# lisa_mac_adb.net
KiCad netlist of a schematic drawn in EAGLE
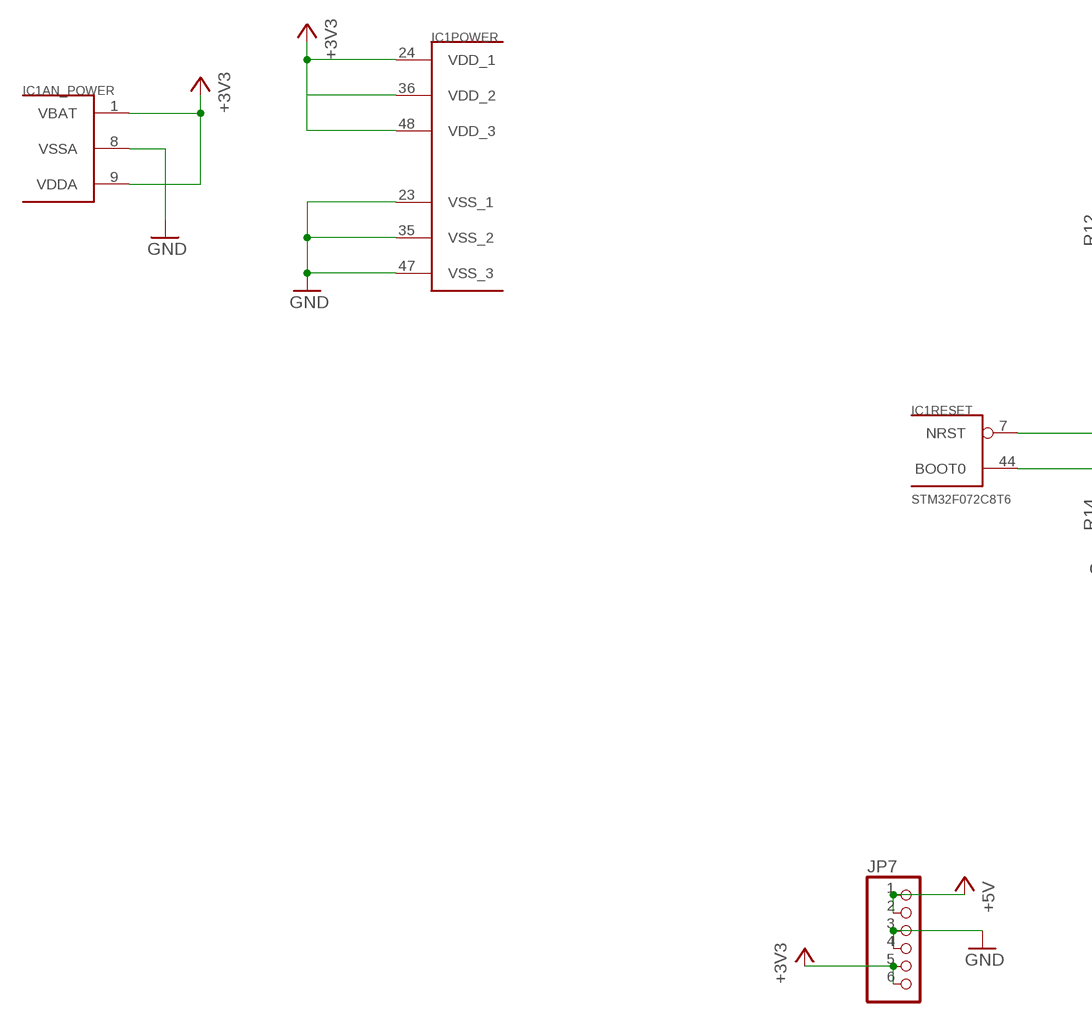
[diagram p0: schematic, sheet 1, part 1 of 2]
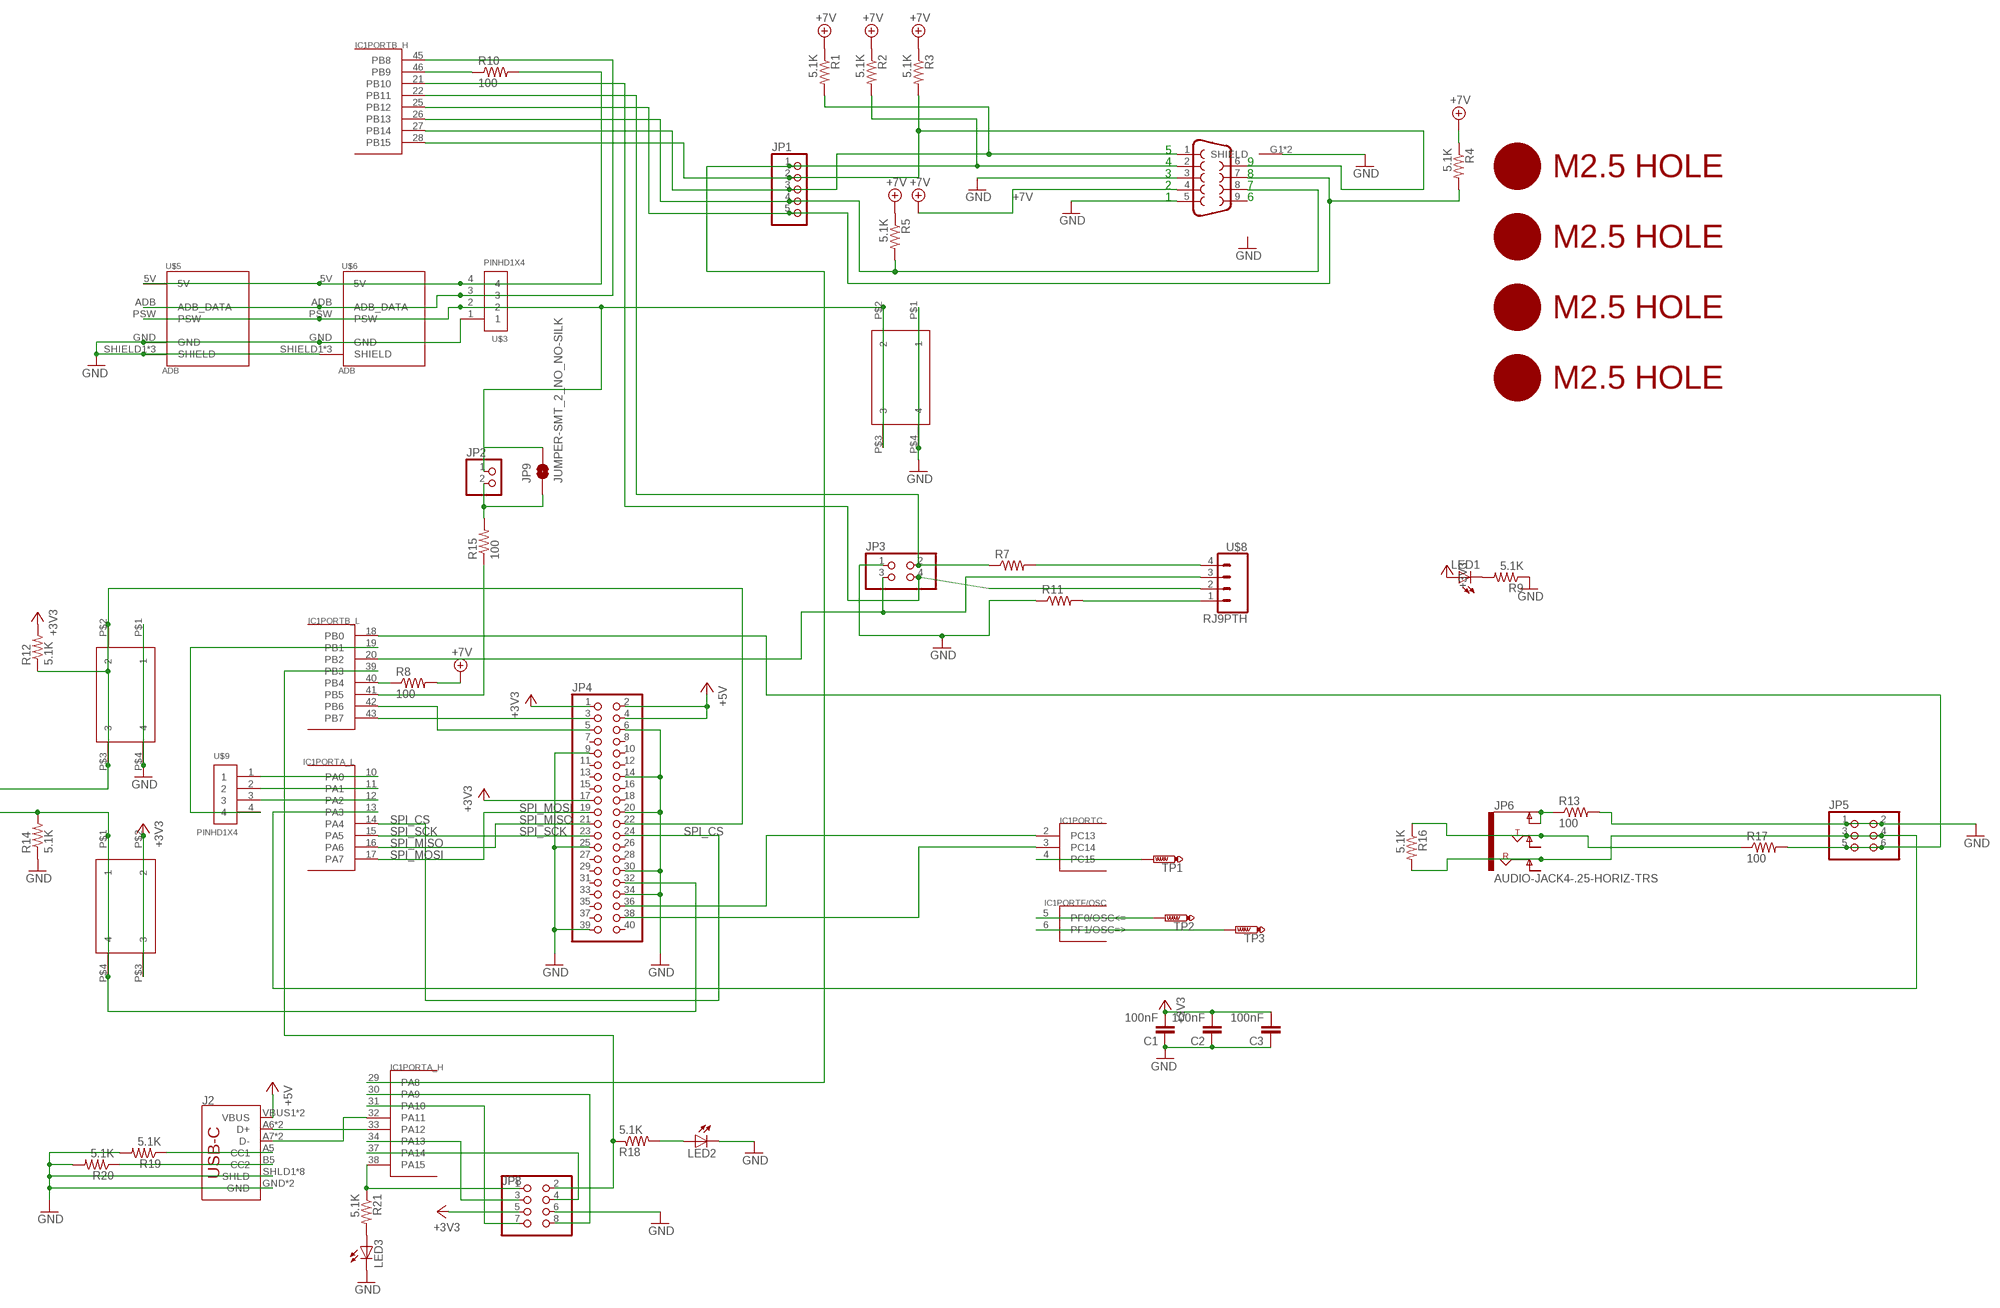
[diagram p1: schematic, sheet 1, part 2 of 2]

(export (version "E")
  (design (tool "Eeschema 10.0.6"))
  (components
    (comp (ref "C1")
      (value "100nF")
      (footprint "eagle-import:0805@1")
      (libsource (lib "eagle-import") (part "CAP0805"))
    )
    (comp (ref "C2")
      (value "100nF")
      (footprint "eagle-import:0805@1")
      (libsource (lib "eagle-import") (part "CAP0805"))
    )
    (comp (ref "C3")
      (value "100nF")
      (footprint "eagle-import:0805@1")
      (libsource (lib "eagle-import") (part "CAP0805"))
    )
    (comp (ref "IC1")
      (value "STM32F072C8T6")
      (footprint "eagle-import:TQFP48")
      (libsource (lib "eagle-import") (part "STM32F072C8T6"))
    )
    (comp (ref "J1")
      (value "DB9FEMALE")
      (footprint "eagle-import:DB9")
      (libsource (lib "eagle-import") (part "DB9FEMALE"))
    )
    (comp (ref "J2")
      (value "USB_C16PIN")
      (footprint "eagle-import:USB-C-16P")
      (libsource (lib "eagle-import") (part "USB_C16PIN"))
    )
    (comp (ref "JP1")
      (value "PINHD-1X5")
      (footprint "eagle-import:1X05")
      (libsource (lib "eagle-import") (part "PINHD-1X5"))
    )
    (comp (ref "JP2")
      (value "PINHD-1X2")
      (footprint "eagle-import:1X02")
      (libsource (lib "eagle-import") (part "PINHD-1X2"))
    )
    (comp (ref "JP3")
      (value "PINHD-2X2")
      (footprint "eagle-import:2X02")
      (libsource (lib "eagle-import") (part "PINHD-2X2"))
    )
    (comp (ref "JP4")
      (value "PINHD-2X20-BIG")
      (footprint "eagle-import:2X20-BIG")
      (libsource (lib "eagle-import") (part "PINHD-2X20-BIG"))
    )
    (comp (ref "JP5")
      (value "PINHD-2X3")
      (footprint "eagle-import:2X03")
      (libsource (lib "eagle-import") (part "PINHD-2X3"))
    )
    (comp (ref "JP6")
      (value "AUDIO-JACK4-.25-HORIZ-TRS")
      (footprint "eagle-import:AUDIO-JACK-.25-INCH-HORIZ-PTH")
      (libsource (lib "eagle-import") (part "AUDIO-JACK4-.25-HORIZ-TRS"))
    )
    (comp (ref "JP7")
      (value "PINHD-1X6CB")
      (footprint "eagle-import:1X06-CLEANBIG")
      (libsource (lib "eagle-import") (part "PINHD-1X6CB"))
    )
    (comp (ref "JP8")
      (value "PINHD-2X4")
      (footprint "eagle-import:2X04")
      (libsource (lib "eagle-import") (part "PINHD-2X4"))
    )
    (comp (ref "JP9")
      (value "JUMPER-SMT_2_NO_NO-SILK")
      (footprint "eagle-import:SMT-JUMPER_2_NO_NO-SILK")
      (libsource (lib "eagle-import") (part "JUMPER-SMT_2_NO_NO-SILK"))
    )
    (comp (ref "LED1")
      (value "LEDCHIP-LED0805")
      (footprint "eagle-import:CHIP-LED0805")
      (libsource (lib "eagle-import") (part "LEDCHIP-LED0805"))
    )
    (comp (ref "LED2")
      (value "LEDCHIP-LED0805")
      (footprint "eagle-import:CHIP-LED0805")
      (libsource (lib "eagle-import") (part "LEDCHIP-LED0805"))
    )
    (comp (ref "LED3")
      (value "LEDCHIP-LED0805")
      (footprint "eagle-import:CHIP-LED0805")
      (libsource (lib "eagle-import") (part "LEDCHIP-LED0805"))
    )
    (comp (ref "R1")
      (value "5.1K")
      (footprint "eagle-import:0805")
      (libsource (lib "eagle-import") (part "RESISTOR0805-RES"))
    )
    (comp (ref "R2")
      (value "5.1K")
      (footprint "eagle-import:0805")
      (libsource (lib "eagle-import") (part "RESISTOR0805-RES"))
    )
    (comp (ref "R3")
      (value "5.1K")
      (footprint "eagle-import:0805")
      (libsource (lib "eagle-import") (part "RESISTOR0805-RES"))
    )
    (comp (ref "R4")
      (value "5.1K")
      (footprint "eagle-import:0805")
      (libsource (lib "eagle-import") (part "RESISTOR0805-RES"))
    )
    (comp (ref "R5")
      (value "5.1K")
      (footprint "eagle-import:0805")
      (libsource (lib "eagle-import") (part "RESISTOR0805-RES"))
    )
    (comp (ref "R7")
      (value "100")
      (footprint "eagle-import:0805")
      (libsource (lib "eagle-import") (part "RESISTOR0805-RES"))
    )
    (comp (ref "R8")
      (value "100")
      (footprint "eagle-import:0805")
      (libsource (lib "eagle-import") (part "RESISTOR0805-RES"))
    )
    (comp (ref "R9")
      (value "5.1K")
      (footprint "eagle-import:0805")
      (libsource (lib "eagle-import") (part "RESISTOR0805-RES"))
    )
    (comp (ref "R10")
      (value "100")
      (footprint "eagle-import:0805")
      (libsource (lib "eagle-import") (part "RESISTOR0805-RES"))
    )
    (comp (ref "R11")
      (value "100")
      (footprint "eagle-import:0805")
      (libsource (lib "eagle-import") (part "RESISTOR0805-RES"))
    )
    (comp (ref "R12")
      (value "5.1K")
      (footprint "eagle-import:0805")
      (libsource (lib "eagle-import") (part "RESISTOR0805-RES"))
    )
    (comp (ref "R13")
      (value "100")
      (footprint "eagle-import:0805")
      (libsource (lib "eagle-import") (part "RESISTOR0805-RES"))
    )
    (comp (ref "R14")
      (value "5.1K")
      (footprint "eagle-import:0805")
      (libsource (lib "eagle-import") (part "RESISTOR0805-RES"))
    )
    (comp (ref "R15")
      (value "100")
      (footprint "eagle-import:0805")
      (libsource (lib "eagle-import") (part "RESISTOR0805-RES"))
    )
    (comp (ref "R16")
      (value "5.1K")
      (footprint "eagle-import:0805")
      (libsource (lib "eagle-import") (part "RESISTOR0805-RES"))
    )
    (comp (ref "R17")
      (value "100")
      (footprint "eagle-import:0805")
      (libsource (lib "eagle-import") (part "RESISTOR0805-RES"))
    )
    (comp (ref "R18")
      (value "5.1K")
      (footprint "eagle-import:0805")
      (libsource (lib "eagle-import") (part "RESISTOR0805-RES"))
    )
    (comp (ref "R19")
      (value "5.1K")
      (footprint "eagle-import:0805")
      (libsource (lib "eagle-import") (part "RESISTOR0805-RES"))
    )
    (comp (ref "R20")
      (value "5.1K")
      (footprint "eagle-import:0805")
      (libsource (lib "eagle-import") (part "RESISTOR0805-RES"))
    )
    (comp (ref "R21")
      (value "5.1K")
      (footprint "eagle-import:0805")
      (libsource (lib "eagle-import") (part "RESISTOR0805-RES"))
    )
    (comp (ref "SW1")
      (value "324_SW")
      (footprint "eagle-import:342_SWICH_FOOT")
      (libsource (lib "eagle-import") (part "324_SW"))
    )
    (comp (ref "SW2")
      (value "324_SW")
      (footprint "eagle-import:342_SWICH_FOOT")
      (libsource (lib "eagle-import") (part "324_SW"))
    )
    (comp (ref "SW3")
      (value "324_SW")
      (footprint "eagle-import:342_SWICH_FOOT")
      (libsource (lib "eagle-import") (part "324_SW"))
    )
    (comp (ref "TP1")
      (value "PTR1TP14R")
      (footprint "eagle-import:TP14R")
      (libsource (lib "eagle-import") (part "PTR1TP14R"))
    )
    (comp (ref "TP2")
      (value "PTR1TP14R")
      (footprint "eagle-import:TP14R")
      (libsource (lib "eagle-import") (part "PTR1TP14R"))
    )
    (comp (ref "TP3")
      (value "PTR1TP14R")
      (footprint "eagle-import:TP14R")
      (libsource (lib "eagle-import") (part "PTR1TP14R"))
    )
    (comp (ref "U$1")
      (value "M2.5HOLE")
      (footprint "eagle-import:M2.5HOLE")
      (libsource (lib "eagle-import") (part "M2.5HOLE"))
    )
    (comp (ref "U$2")
      (value "M2.5HOLE")
      (footprint "eagle-import:M2.5HOLE")
      (libsource (lib "eagle-import") (part "M2.5HOLE"))
    )
    (comp (ref "U$3")
      (value "PINHD1X4")
      (footprint "eagle-import:1X04-CLEANBIG")
      (libsource (lib "eagle-import") (part "PINHD1X4"))
    )
    (comp (ref "U$4")
      (value "M2.5HOLE")
      (footprint "eagle-import:M2.5HOLE")
      (libsource (lib "eagle-import") (part "M2.5HOLE"))
    )
    (comp (ref "U$5")
      (value "ADB")
      (footprint "eagle-import:DIN4")
      (libsource (lib "eagle-import") (part "ADB"))
    )
    (comp (ref "U$6")
      (value "ADB")
      (footprint "eagle-import:DIN4")
      (libsource (lib "eagle-import") (part "ADB"))
    )
    (comp (ref "U$7")
      (value "M2.5HOLE")
      (footprint "eagle-import:M2.5HOLE")
      (libsource (lib "eagle-import") (part "M2.5HOLE"))
    )
    (comp (ref "U$8")
      (value "RJ9PTH")
      (footprint "eagle-import:RJ9")
      (libsource (lib "eagle-import") (part "RJ9PTH"))
    )
    (comp (ref "U$9")
      (value "PINHD1X4")
      (footprint "eagle-import:1X04-CLEANBIG")
      (libsource (lib "eagle-import") (part "PINHD1X4"))
    )
  )
  (nets
    (net (code "1") (name "+3V3") (class "Default")
      (node (ref "C1") (pin "2") (pinfunction "2_2") (pintype "passive"))
      (node (ref "C2") (pin "2") (pinfunction "2_2") (pintype "passive"))
      (node (ref "C3") (pin "2") (pinfunction "2_2") (pintype "passive"))
      (node (ref "IC1") (pin "1") (pinfunction "VBAT_1") (pintype "power_in"))
      (node (ref "IC1") (pin "24") (pinfunction "VDD_1_24") (pintype "power_in"))
      (node (ref "IC1") (pin "36") (pinfunction "VDD_2_36") (pintype "power_in"))
      (node (ref "IC1") (pin "48") (pinfunction "VDD_3_48") (pintype "power_in"))
      (node (ref "IC1") (pin "9") (pinfunction "VDDA_9") (pintype "power_in"))
      (node (ref "JP4") (pin "1") (pinfunction "1_1") (pintype "passive"))
      (node (ref "JP4") (pin "17") (pinfunction "17_17") (pintype "passive"))
      (node (ref "JP7") (pin "5") (pinfunction "5_5") (pintype "passive"))
      (node (ref "JP7") (pin "6") (pinfunction "6_6") (pintype "passive"))
      (node (ref "JP8") (pin "5") (pinfunction "5_5") (pintype "passive"))
      (node (ref "LED1") (pin "A") (pinfunction "A_A") (pintype "passive"))
      (node (ref "R12") (pin "2") (pinfunction "2_2") (pintype "passive"))
      (node (ref "SW3") (pin "P$2") (pinfunction "2_P$2") (pintype "bidirectional"))
      (node (ref "SW3") (pin "P$3") (pinfunction "3_P$3") (pintype "bidirectional"))
    )
    (net (code "2") (name "+5V") (class "Default")
      (node (ref "J2") (pin "VBUS1") (pinfunction "VBUS_VBUS1") (pintype "bidirectional"))
      (node (ref "J2") (pin "VBUS2") (pinfunction "VBUS_VBUS2") (pintype "bidirectional"))
      (node (ref "JP4") (pin "2") (pinfunction "2_2") (pintype "passive"))
      (node (ref "JP4") (pin "4") (pinfunction "4_4") (pintype "passive"))
      (node (ref "JP7") (pin "1") (pinfunction "1_1") (pintype "passive"))
      (node (ref "JP7") (pin "2") (pinfunction "2_2") (pintype "passive"))
    )
    (net (code "3") (name "+7V") (class "Default")
      (node (ref "J1") (pin "4") (pinfunction "4_4") (pintype "passive"))
      (node (ref "R1") (pin "1") (pinfunction "1_1") (pintype "passive"))
      (node (ref "R2") (pin "1") (pinfunction "1_1") (pintype "passive"))
      (node (ref "R3") (pin "1") (pinfunction "1_1") (pintype "passive"))
      (node (ref "R4") (pin "1") (pinfunction "1_1") (pintype "passive"))
      (node (ref "R5") (pin "1") (pinfunction "1_1") (pintype "passive"))
      (node (ref "R8") (pin "2") (pinfunction "2_2") (pintype "passive"))
    )
    (net (code "4") (name "/SPI_CS") (class "Default")
      (node (ref "IC1") (pin "14") (pinfunction "PA4_14") (pintype "bidirectional"))
      (node (ref "JP4") (pin "24") (pinfunction "24_24") (pintype "passive"))
    )
    (net (code "5") (name "/SPI_MISO") (class "Default")
      (node (ref "IC1") (pin "16") (pinfunction "PA6_16") (pintype "bidirectional"))
      (node (ref "JP4") (pin "21") (pinfunction "21_21") (pintype "passive"))
    )
    (net (code "6") (name "/SPI_MOSI") (class "Default")
      (node (ref "IC1") (pin "17") (pinfunction "PA7_17") (pintype "bidirectional"))
      (node (ref "JP4") (pin "19") (pinfunction "19_19") (pintype "passive"))
    )
    (net (code "7") (name "/SPI_SCK") (class "Default")
      (node (ref "IC1") (pin "15") (pinfunction "PA5_15") (pintype "bidirectional"))
      (node (ref "JP4") (pin "23") (pinfunction "23_23") (pintype "passive"))
    )
    (net (code "8") (name "GND") (class "Default")
      (node (ref "C1") (pin "1") (pinfunction "1_1") (pintype "passive"))
      (node (ref "C2") (pin "1") (pinfunction "1_1") (pintype "passive"))
      (node (ref "C3") (pin "1") (pinfunction "1_1") (pintype "passive"))
      (node (ref "IC1") (pin "23") (pinfunction "VSS_1_23") (pintype "power_in"))
      (node (ref "IC1") (pin "35") (pinfunction "VSS_2_35") (pintype "power_in"))
      (node (ref "IC1") (pin "47") (pinfunction "VSS_3_47") (pintype "power_in"))
      (node (ref "IC1") (pin "8") (pinfunction "VSSA_8") (pintype "power_in"))
      (node (ref "J1") (pin "3") (pinfunction "3_3") (pintype "passive"))
      (node (ref "J1") (pin "5") (pinfunction "5_5") (pintype "passive"))
      (node (ref "J1") (pin "G1") (pinfunction "SHIELD_G1") (pintype "bidirectional"))
      (node (ref "J1") (pin "G2") (pinfunction "SHIELD_G2") (pintype "bidirectional"))
      (node (ref "J2") (pin "GND") (pinfunction "GND_GND") (pintype "bidirectional"))
      (node (ref "J2") (pin "GND2") (pinfunction "GND_GND2") (pintype "bidirectional"))
      (node (ref "J2") (pin "SHLD1") (pinfunction "SHLD_SHLD1") (pintype "bidirectional"))
      (node (ref "J2") (pin "SHLD2") (pinfunction "SHLD_SHLD2") (pintype "bidirectional"))
      (node (ref "J2") (pin "SHLD3") (pinfunction "SHLD_SHLD3") (pintype "bidirectional"))
      (node (ref "J2") (pin "SHLD4") (pinfunction "SHLD_SHLD4") (pintype "bidirectional"))
      (node (ref "J2") (pin "SHLD5") (pinfunction "SHLD_SHLD5") (pintype "bidirectional"))
      (node (ref "J2") (pin "SHLD6") (pinfunction "SHLD_SHLD6") (pintype "bidirectional"))
      (node (ref "J2") (pin "SHLD7") (pinfunction "SHLD_SHLD7") (pintype "bidirectional"))
      (node (ref "J2") (pin "SHLD8") (pinfunction "SHLD_SHLD8") (pintype "bidirectional"))
      (node (ref "JP3") (pin "1") (pinfunction "1_1") (pintype "passive"))
      (node (ref "JP4") (pin "14") (pinfunction "14_14") (pintype "passive"))
      (node (ref "JP4") (pin "20") (pinfunction "20_20") (pintype "passive"))
      (node (ref "JP4") (pin "25") (pinfunction "25_25") (pintype "passive"))
      (node (ref "JP4") (pin "30") (pinfunction "30_30") (pintype "passive"))
      (node (ref "JP4") (pin "34") (pinfunction "34_34") (pintype "passive"))
      (node (ref "JP4") (pin "39") (pinfunction "39_39") (pintype "passive"))
      (node (ref "JP4") (pin "6") (pinfunction "6_6") (pintype "passive"))
      (node (ref "JP4") (pin "9") (pinfunction "9_9") (pintype "passive"))
      (node (ref "JP5") (pin "1") (pinfunction "1_1") (pintype "passive"))
      (node (ref "JP5") (pin "2") (pinfunction "2_2") (pintype "passive"))
      (node (ref "JP7") (pin "3") (pinfunction "3_3") (pintype "passive"))
      (node (ref "JP7") (pin "4") (pinfunction "4_4") (pintype "passive"))
      (node (ref "JP8") (pin "6") (pinfunction "6_6") (pintype "passive"))
      (node (ref "LED2") (pin "C") (pinfunction "C_C") (pintype "passive"))
      (node (ref "LED3") (pin "C") (pinfunction "C_C") (pintype "passive"))
      (node (ref "R11") (pin "1") (pinfunction "1_1") (pintype "passive"))
      (node (ref "R13") (pin "2") (pinfunction "2_2") (pintype "passive"))
      (node (ref "R14") (pin "1") (pinfunction "1_1") (pintype "passive"))
      (node (ref "R19") (pin "2") (pinfunction "2_2") (pintype "passive"))
      (node (ref "R20") (pin "2") (pinfunction "2_2") (pintype "passive"))
      (node (ref "R9") (pin "1") (pinfunction "1_1") (pintype "passive"))
      (node (ref "SW1") (pin "P$1") (pinfunction "1_P$1") (pintype "bidirectional"))
      (node (ref "SW1") (pin "P$4") (pinfunction "4_P$4") (pintype "bidirectional"))
      (node (ref "SW2") (pin "P$1") (pinfunction "1_P$1") (pintype "bidirectional"))
      (node (ref "SW2") (pin "P$4") (pinfunction "4_P$4") (pintype "bidirectional"))
      (node (ref "U$3") (pin "1") (pinfunction "1_1") (pintype "bidirectional"))
      (node (ref "U$5") (pin "GND") (pinfunction "GND_GND") (pintype "bidirectional"))
      (node (ref "U$5") (pin "SHIELD1") (pinfunction "SHIELD_SHIELD1") (pintype "bidirectional"))
      (node (ref "U$5") (pin "SHIELD2") (pinfunction "SHIELD_SHIELD2") (pintype "bidirectional"))
      (node (ref "U$5") (pin "SHIELD3") (pinfunction "SHIELD_SHIELD3") (pintype "bidirectional"))
      (node (ref "U$6") (pin "GND") (pinfunction "GND_GND") (pintype "bidirectional"))
      (node (ref "U$6") (pin "SHIELD1") (pinfunction "SHIELD_SHIELD1") (pintype "bidirectional"))
      (node (ref "U$6") (pin "SHIELD2") (pinfunction "SHIELD_SHIELD2") (pintype "bidirectional"))
      (node (ref "U$6") (pin "SHIELD3") (pinfunction "SHIELD_SHIELD3") (pintype "bidirectional"))
    )
    (net (code "9") (name "Net-(IC1B-PA8)") (class "Default")
      (node (ref "IC1") (pin "29") (pinfunction "PA8_29") (pintype "bidirectional"))
      (node (ref "J1") (pin "2") (pinfunction "2_2") (pintype "passive"))
      (node (ref "JP1") (pin "1") (pinfunction "1_1") (pintype "passive"))
      (node (ref "R2") (pin "2") (pinfunction "2_2") (pintype "passive"))
    )
    (net (code "10") (name "Net-(IC1B-PA9)") (class "Default")
      (node (ref "IC1") (pin "30") (pinfunction "PA9_30") (pintype "bidirectional"))
      (node (ref "JP8") (pin "8") (pinfunction "8_8") (pintype "passive"))
    )
    (net (code "11") (name "Net-(IC1B-PA10)") (class "Default")
      (node (ref "IC1") (pin "31") (pinfunction "PA10_31") (pintype "bidirectional"))
      (node (ref "JP8") (pin "7") (pinfunction "7_7") (pintype "passive"))
    )
    (net (code "12") (name "Net-(IC1B-PA11)") (class "Default")
      (node (ref "IC1") (pin "32") (pinfunction "PA11_32") (pintype "bidirectional"))
      (node (ref "J2") (pin "A7") (pinfunction "D-_A7") (pintype "bidirectional"))
      (node (ref "J2") (pin "B7") (pinfunction "D-_B7") (pintype "bidirectional"))
    )
    (net (code "13") (name "Net-(IC1B-PA12)") (class "Default")
      (node (ref "IC1") (pin "33") (pinfunction "PA12_33") (pintype "bidirectional"))
      (node (ref "J2") (pin "A6") (pinfunction "D+_A6") (pintype "bidirectional"))
      (node (ref "J2") (pin "B6") (pinfunction "D+_B6") (pintype "bidirectional"))
    )
    (net (code "14") (name "Net-(IC1B-PA13)") (class "Default")
      (node (ref "IC1") (pin "34") (pinfunction "PA13_34") (pintype "bidirectional"))
      (node (ref "JP8") (pin "3") (pinfunction "3_3") (pintype "passive"))
    )
    (net (code "15") (name "Net-(IC1B-PA14)") (class "Default")
      (node (ref "IC1") (pin "37") (pinfunction "PA14_37") (pintype "bidirectional"))
      (node (ref "JP8") (pin "4") (pinfunction "4_4") (pintype "passive"))
    )
    (net (code "16") (name "Net-(IC1B-PA15)") (class "Default")
      (node (ref "IC1") (pin "38") (pinfunction "PA15_38") (pintype "bidirectional"))
      (node (ref "JP8") (pin "1") (pinfunction "1_1") (pintype "passive"))
      (node (ref "R21") (pin "1") (pinfunction "1_1") (pintype "passive"))
    )
    (net (code "17") (name "Net-(IC1C-PA0)") (class "Default")
      (node (ref "IC1") (pin "10") (pinfunction "PA0_10") (pintype "bidirectional"))
      (node (ref "U$9") (pin "1") (pinfunction "1_1") (pintype "bidirectional"))
    )
    (net (code "18") (name "Net-(IC1C-PA1)") (class "Default")
      (node (ref "IC1") (pin "11") (pinfunction "PA1_11") (pintype "bidirectional"))
      (node (ref "U$9") (pin "2") (pinfunction "2_2") (pintype "bidirectional"))
    )
    (net (code "19") (name "Net-(IC1C-PA2)") (class "Default")
      (node (ref "IC1") (pin "12") (pinfunction "PA2_12") (pintype "bidirectional"))
      (node (ref "U$9") (pin "3") (pinfunction "3_3") (pintype "bidirectional"))
    )
    (net (code "20") (name "Net-(IC1C-PA3)") (class "Default")
      (node (ref "IC1") (pin "13") (pinfunction "PA3_13") (pintype "bidirectional"))
      (node (ref "JP5") (pin "3") (pinfunction "3_3") (pintype "passive"))
      (node (ref "JP5") (pin "4") (pinfunction "4_4") (pintype "passive"))
      (node (ref "JP6") (pin "RING") (pinfunction "RING_RING") (pintype "bidirectional"))
      (node (ref "R16") (pin "2") (pinfunction "2_2") (pintype "passive"))
    )
    (net (code "21") (name "Net-(IC1D-PB8)") (class "Default")
      (node (ref "IC1") (pin "45") (pinfunction "PB8_45") (pintype "bidirectional"))
      (node (ref "U$3") (pin "3") (pinfunction "3_3") (pintype "bidirectional"))
      (node (ref "U$5") (pin "ADB") (pinfunction "ADB_DATA_ADB") (pintype "bidirectional"))
      (node (ref "U$6") (pin "ADB") (pinfunction "ADB_DATA_ADB") (pintype "bidirectional"))
    )
    (net (code "22") (name "Net-(IC1D-PB9)") (class "Default")
      (node (ref "IC1") (pin "46") (pinfunction "PB9_46") (pintype "bidirectional"))
      (node (ref "R10") (pin "1") (pinfunction "1_1") (pintype "passive"))
    )
    (net (code "23") (name "Net-(IC1D-PB10)") (class "Default")
      (node (ref "IC1") (pin "21") (pinfunction "PB10_21") (pintype "bidirectional"))
      (node (ref "JP3") (pin "4") (pinfunction "4_4") (pintype "passive"))
      (node (ref "U$8") (pin "2") (pinfunction "2_2") (pintype "passive"))
    )
    (net (code "24") (name "Net-(IC1D-PB11)") (class "Default")
      (node (ref "IC1") (pin "22") (pinfunction "PB11_22") (pintype "bidirectional"))
      (node (ref "JP3") (pin "2") (pinfunction "2_2") (pintype "passive"))
      (node (ref "R7") (pin "1") (pinfunction "1_1") (pintype "passive"))
    )
    (net (code "25") (name "Net-(IC1D-PB12)") (class "Default")
      (node (ref "IC1") (pin "25") (pinfunction "PB12_25") (pintype "bidirectional"))
      (node (ref "J1") (pin "7") (pinfunction "7_7") (pintype "passive"))
      (node (ref "JP1") (pin "5") (pinfunction "5_5") (pintype "passive"))
      (node (ref "R4") (pin "2") (pinfunction "2_2") (pintype "passive"))
    )
    (net (code "26") (name "Net-(IC1D-PB13)") (class "Default")
      (node (ref "IC1") (pin "26") (pinfunction "PB13_26") (pintype "bidirectional"))
      (node (ref "J1") (pin "8") (pinfunction "8_8") (pintype "passive"))
      (node (ref "JP1") (pin "4") (pinfunction "4_4") (pintype "passive"))
      (node (ref "R5") (pin "2") (pinfunction "2_2") (pintype "passive"))
    )
    (net (code "27") (name "Net-(IC1D-PB14)") (class "Default")
      (node (ref "IC1") (pin "27") (pinfunction "PB14_27") (pintype "bidirectional"))
      (node (ref "J1") (pin "1") (pinfunction "1_1") (pintype "passive"))
      (node (ref "JP1") (pin "3") (pinfunction "3_3") (pintype "passive"))
      (node (ref "R1") (pin "2") (pinfunction "2_2") (pintype "passive"))
    )
    (net (code "28") (name "Net-(IC1D-PB15)") (class "Default")
      (node (ref "IC1") (pin "28") (pinfunction "PB15_28") (pintype "bidirectional"))
      (node (ref "J1") (pin "6") (pinfunction "6_6") (pintype "passive"))
      (node (ref "JP1") (pin "2") (pinfunction "2_2") (pintype "passive"))
      (node (ref "R3") (pin "2") (pinfunction "2_2") (pintype "passive"))
    )
    (net (code "29") (name "Net-(IC1E-PB0)") (class "Default")
      (node (ref "IC1") (pin "18") (pinfunction "PB0_18") (pintype "bidirectional"))
      (node (ref "JP5") (pin "5") (pinfunction "5_5") (pintype "passive"))
      (node (ref "JP5") (pin "6") (pinfunction "6_6") (pintype "passive"))
      (node (ref "R17") (pin "2") (pinfunction "2_2") (pintype "passive"))
    )
    (net (code "30") (name "Net-(IC1E-PB1)") (class "Default")
      (node (ref "IC1") (pin "19") (pinfunction "PB1_19") (pintype "bidirectional"))
      (node (ref "U$9") (pin "4") (pinfunction "4_4") (pintype "bidirectional"))
    )
    (net (code "31") (name "Net-(IC1E-PB2)") (class "Default")
      (node (ref "IC1") (pin "20") (pinfunction "PB2_20") (pintype "bidirectional"))
      (node (ref "JP3") (pin "3") (pinfunction "3_3") (pintype "passive"))
      (node (ref "U$8") (pin "3") (pinfunction "3_3") (pintype "passive"))
    )
    (net (code "32") (name "Net-(IC1E-PB3)") (class "Default")
      (node (ref "IC1") (pin "39") (pinfunction "PB3_39") (pintype "bidirectional"))
      (node (ref "JP8") (pin "2") (pinfunction "2_2") (pintype "passive"))
      (node (ref "R18") (pin "1") (pinfunction "1_1") (pintype "passive"))
    )
    (net (code "33") (name "Net-(IC1E-PB4)") (class "Default")
      (node (ref "IC1") (pin "40") (pinfunction "PB4_40") (pintype "bidirectional"))
      (node (ref "R8") (pin "1") (pinfunction "1_1") (pintype "passive"))
    )
    (net (code "34") (name "Net-(IC1E-PB5)") (class "Default")
      (node (ref "IC1") (pin "41") (pinfunction "PB5_41") (pintype "bidirectional"))
      (node (ref "R15") (pin "1") (pinfunction "1_1") (pintype "passive"))
    )
    (net (code "35") (name "Net-(IC1E-PB6)") (class "Default")
      (node (ref "IC1") (pin "42") (pinfunction "PB6_42") (pintype "bidirectional"))
      (node (ref "JP4") (pin "5") (pinfunction "5_5") (pintype "passive"))
    )
    (net (code "36") (name "Net-(IC1E-PB7)") (class "Default")
      (node (ref "IC1") (pin "43") (pinfunction "PB7_43") (pintype "bidirectional"))
      (node (ref "JP4") (pin "3") (pinfunction "3_3") (pintype "passive"))
    )
    (net (code "37") (name "Net-(IC1F-PC13)") (class "Default")
      (node (ref "IC1") (pin "2") (pinfunction "PC13_2") (pintype "bidirectional"))
      (node (ref "JP4") (pin "36") (pinfunction "36_36") (pintype "passive"))
    )
    (net (code "38") (name "Net-(IC1F-PC14)") (class "Default")
      (node (ref "IC1") (pin "3") (pinfunction "PC14_3") (pintype "bidirectional"))
      (node (ref "JP4") (pin "38") (pinfunction "38_38") (pintype "passive"))
    )
    (net (code "39") (name "Net-(IC1F-PC15)") (class "Default")
      (node (ref "IC1") (pin "4") (pinfunction "PC15_4") (pintype "bidirectional"))
      (node (ref "TP1") (pin "TP") (pinfunction "TP_TP") (pintype "input"))
    )
    (net (code "40") (name "Net-(IC1G-PF0{slash}OSC<=)") (class "Default")
      (node (ref "IC1") (pin "5") (pinfunction "PF0/OSC<=_5") (pintype "bidirectional"))
      (node (ref "TP2") (pin "TP") (pinfunction "TP_TP") (pintype "input"))
    )
    (net (code "41") (name "Net-(IC1G-PF1{slash}OSC=>)") (class "Default")
      (node (ref "IC1") (pin "6") (pinfunction "PF1/OSC=>_6") (pintype "bidirectional"))
      (node (ref "TP3") (pin "TP") (pinfunction "TP_TP") (pintype "input"))
    )
    (net (code "42") (name "Net-(IC1I-BOOT0)") (class "Default")
      (node (ref "IC1") (pin "44") (pinfunction "BOOT0_44") (pintype "input"))
      (node (ref "JP4") (pin "32") (pinfunction "32_32") (pintype "passive"))
      (node (ref "R14") (pin "2") (pinfunction "2_2") (pintype "passive"))
      (node (ref "SW3") (pin "P$1") (pinfunction "1_P$1") (pintype "bidirectional"))
      (node (ref "SW3") (pin "P$4") (pinfunction "4_P$4") (pintype "bidirectional"))
    )
    (net (code "43") (name "Net-(IC1I-NRST)") (class "Default")
      (node (ref "IC1") (pin "7") (pinfunction "NRST_7") (pintype "input"))
      (node (ref "JP4") (pin "22") (pinfunction "22_22") (pintype "passive"))
      (node (ref "R12") (pin "1") (pinfunction "1_1") (pintype "passive"))
      (node (ref "SW2") (pin "P$2") (pinfunction "2_P$2") (pintype "bidirectional"))
      (node (ref "SW2") (pin "P$3") (pinfunction "3_P$3") (pintype "bidirectional"))
    )
    (net (code "44") (name "Net-(J2-CC1)") (class "Default")
      (node (ref "J2") (pin "A5") (pinfunction "CC1_A5") (pintype "bidirectional"))
      (node (ref "R19") (pin "1") (pinfunction "1_1") (pintype "passive"))
    )
    (net (code "45") (name "Net-(J2-CC2)") (class "Default")
      (node (ref "J2") (pin "B5") (pinfunction "CC2_B5") (pintype "bidirectional"))
      (node (ref "R20") (pin "1") (pinfunction "1_1") (pintype "passive"))
    )
    (net (code "46") (name "Net-(JP2-Pad2)") (class "Default")
      (node (ref "JP2") (pin "2") (pinfunction "2_2") (pintype "passive"))
      (node (ref "JP9") (pin "1") (pinfunction "1_1") (pintype "passive"))
      (node (ref "R15") (pin "2") (pinfunction "2_2") (pintype "passive"))
    )
    (net (code "47") (name "Net-(JP6-EARTH)") (class "Default")
      (node (ref "JP6") (pin "SLEEVE") (pinfunction "EARTH_SLEEVE") (pintype "bidirectional"))
      (node (ref "JP6") (pin "SLEEVE-NORM") (pinfunction "EARTH-NORM_SLEEVE-NORM") (pintype "bidirectional"))
      (node (ref "R13") (pin "1") (pinfunction "1_1") (pintype "passive"))
    )
    (net (code "48") (name "Net-(JP6-PadTIP)") (class "Default")
      (node (ref "JP6") (pin "TIP") (pinfunction "TIP_TIP") (pintype "bidirectional"))
      (node (ref "R16") (pin "1") (pinfunction "1_1") (pintype "passive"))
      (node (ref "R17") (pin "1") (pinfunction "1_1") (pintype "passive"))
    )
    (net (code "49") (name "Net-(LED1-PadC)") (class "Default")
      (node (ref "LED1") (pin "C") (pinfunction "C_C") (pintype "passive"))
      (node (ref "R9") (pin "2") (pinfunction "2_2") (pintype "passive"))
    )
    (net (code "50") (name "Net-(LED2-PadA)") (class "Default")
      (node (ref "LED2") (pin "A") (pinfunction "A_A") (pintype "passive"))
      (node (ref "R18") (pin "2") (pinfunction "2_2") (pintype "passive"))
    )
    (net (code "51") (name "Net-(LED3-PadA)") (class "Default")
      (node (ref "LED3") (pin "A") (pinfunction "A_A") (pintype "passive"))
      (node (ref "R21") (pin "2") (pinfunction "2_2") (pintype "passive"))
    )
    (net (code "52") (name "Net-(R7-Pad2)") (class "Default")
      (node (ref "R7") (pin "2") (pinfunction "2_2") (pintype "passive"))
      (node (ref "U$8") (pin "4") (pinfunction "4_4") (pintype "passive"))
    )
    (net (code "53") (name "Net-(R10-Pad2)") (class "Default")
      (node (ref "R10") (pin "2") (pinfunction "2_2") (pintype "passive"))
      (node (ref "U$3") (pin "4") (pinfunction "4_4") (pintype "bidirectional"))
      (node (ref "U$5") (pin "5V") (pinfunction "5V_5V") (pintype "bidirectional"))
      (node (ref "U$6") (pin "5V") (pinfunction "5V_5V") (pintype "bidirectional"))
    )
    (net (code "54") (name "Net-(R11-Pad2)") (class "Default")
      (node (ref "R11") (pin "2") (pinfunction "2_2") (pintype "passive"))
      (node (ref "U$8") (pin "1") (pinfunction "1_1") (pintype "passive"))
    )
    (net (code "55") (name "Net-(SW1-2)") (class "Default")
      (node (ref "JP2") (pin "1") (pinfunction "1_1") (pintype "passive"))
      (node (ref "JP9") (pin "2") (pinfunction "2_2") (pintype "passive"))
      (node (ref "SW1") (pin "P$2") (pinfunction "2_P$2") (pintype "bidirectional"))
      (node (ref "SW1") (pin "P$3") (pinfunction "3_P$3") (pintype "bidirectional"))
      (node (ref "U$3") (pin "2") (pinfunction "2_2") (pintype "bidirectional"))
      (node (ref "U$5") (pin "PSW") (pinfunction "PSW_PSW") (pintype "bidirectional"))
      (node (ref "U$6") (pin "PSW") (pinfunction "PSW_PSW") (pintype "bidirectional"))
    )
    (net (code "56") (name "unconnected-(J1-Pad9)") (class "Default")
      (node (ref "J1") (pin "9") (pinfunction "9_9") (pintype "passive"))
    )
    (net (code "57") (name "unconnected-(JP4-Pad7)") (class "Default")
      (node (ref "JP4") (pin "7") (pinfunction "7_7") (pintype "passive"))
    )
    (net (code "58") (name "unconnected-(JP4-Pad8)") (class "Default")
      (node (ref "JP4") (pin "8") (pinfunction "8_8") (pintype "passive"))
    )
    (net (code "59") (name "unconnected-(JP4-Pad10)") (class "Default")
      (node (ref "JP4") (pin "10") (pinfunction "10_10") (pintype "passive"))
    )
    (net (code "60") (name "unconnected-(JP4-Pad11)") (class "Default")
      (node (ref "JP4") (pin "11") (pinfunction "11_11") (pintype "passive"))
    )
    (net (code "61") (name "unconnected-(JP4-Pad12)") (class "Default")
      (node (ref "JP4") (pin "12") (pinfunction "12_12") (pintype "passive"))
    )
    (net (code "62") (name "unconnected-(JP4-Pad13)") (class "Default")
      (node (ref "JP4") (pin "13") (pinfunction "13_13") (pintype "passive"))
    )
    (net (code "63") (name "unconnected-(JP4-Pad15)") (class "Default")
      (node (ref "JP4") (pin "15") (pinfunction "15_15") (pintype "passive"))
    )
    (net (code "64") (name "unconnected-(JP4-Pad16)") (class "Default")
      (node (ref "JP4") (pin "16") (pinfunction "16_16") (pintype "passive"))
    )
    (net (code "65") (name "unconnected-(JP4-Pad18)") (class "Default")
      (node (ref "JP4") (pin "18") (pinfunction "18_18") (pintype "passive"))
    )
    (net (code "66") (name "unconnected-(JP4-Pad26)") (class "Default")
      (node (ref "JP4") (pin "26") (pinfunction "26_26") (pintype "passive"))
    )
    (net (code "67") (name "unconnected-(JP4-Pad27)") (class "Default")
      (node (ref "JP4") (pin "27") (pinfunction "27_27") (pintype "passive"))
    )
    (net (code "68") (name "unconnected-(JP4-Pad28)") (class "Default")
      (node (ref "JP4") (pin "28") (pinfunction "28_28") (pintype "passive"))
    )
    (net (code "69") (name "unconnected-(JP4-Pad29)") (class "Default")
      (node (ref "JP4") (pin "29") (pinfunction "29_29") (pintype "passive"))
    )
    (net (code "70") (name "unconnected-(JP4-Pad31)") (class "Default")
      (node (ref "JP4") (pin "31") (pinfunction "31_31") (pintype "passive"))
    )
    (net (code "71") (name "unconnected-(JP4-Pad33)") (class "Default")
      (node (ref "JP4") (pin "33") (pinfunction "33_33") (pintype "passive"))
    )
    (net (code "72") (name "unconnected-(JP4-Pad35)") (class "Default")
      (node (ref "JP4") (pin "35") (pinfunction "35_35") (pintype "passive"))
    )
    (net (code "73") (name "unconnected-(JP4-Pad37)") (class "Default")
      (node (ref "JP4") (pin "37") (pinfunction "37_37") (pintype "passive"))
    )
    (net (code "74") (name "unconnected-(JP4-Pad40)") (class "Default")
      (node (ref "JP4") (pin "40") (pinfunction "40_40") (pintype "passive"))
    )
    (net (code "75") (name "unconnected-(JP6-PadRING-NORM)") (class "Default")
      (node (ref "JP6") (pin "RING-NORM") (pinfunction "RING-NORM_RING-NORM") (pintype "bidirectional"))
    )
    (net (code "76") (name "unconnected-(JP6-PadTIP-NORM)") (class "Default")
      (node (ref "JP6") (pin "TIP-NORM") (pinfunction "TIP-NORM_TIP-NORM") (pintype "bidirectional"))
    )
  )
)
